# display_device_for_board.net
KiCad netlist of a schematic drawn in EAGLE
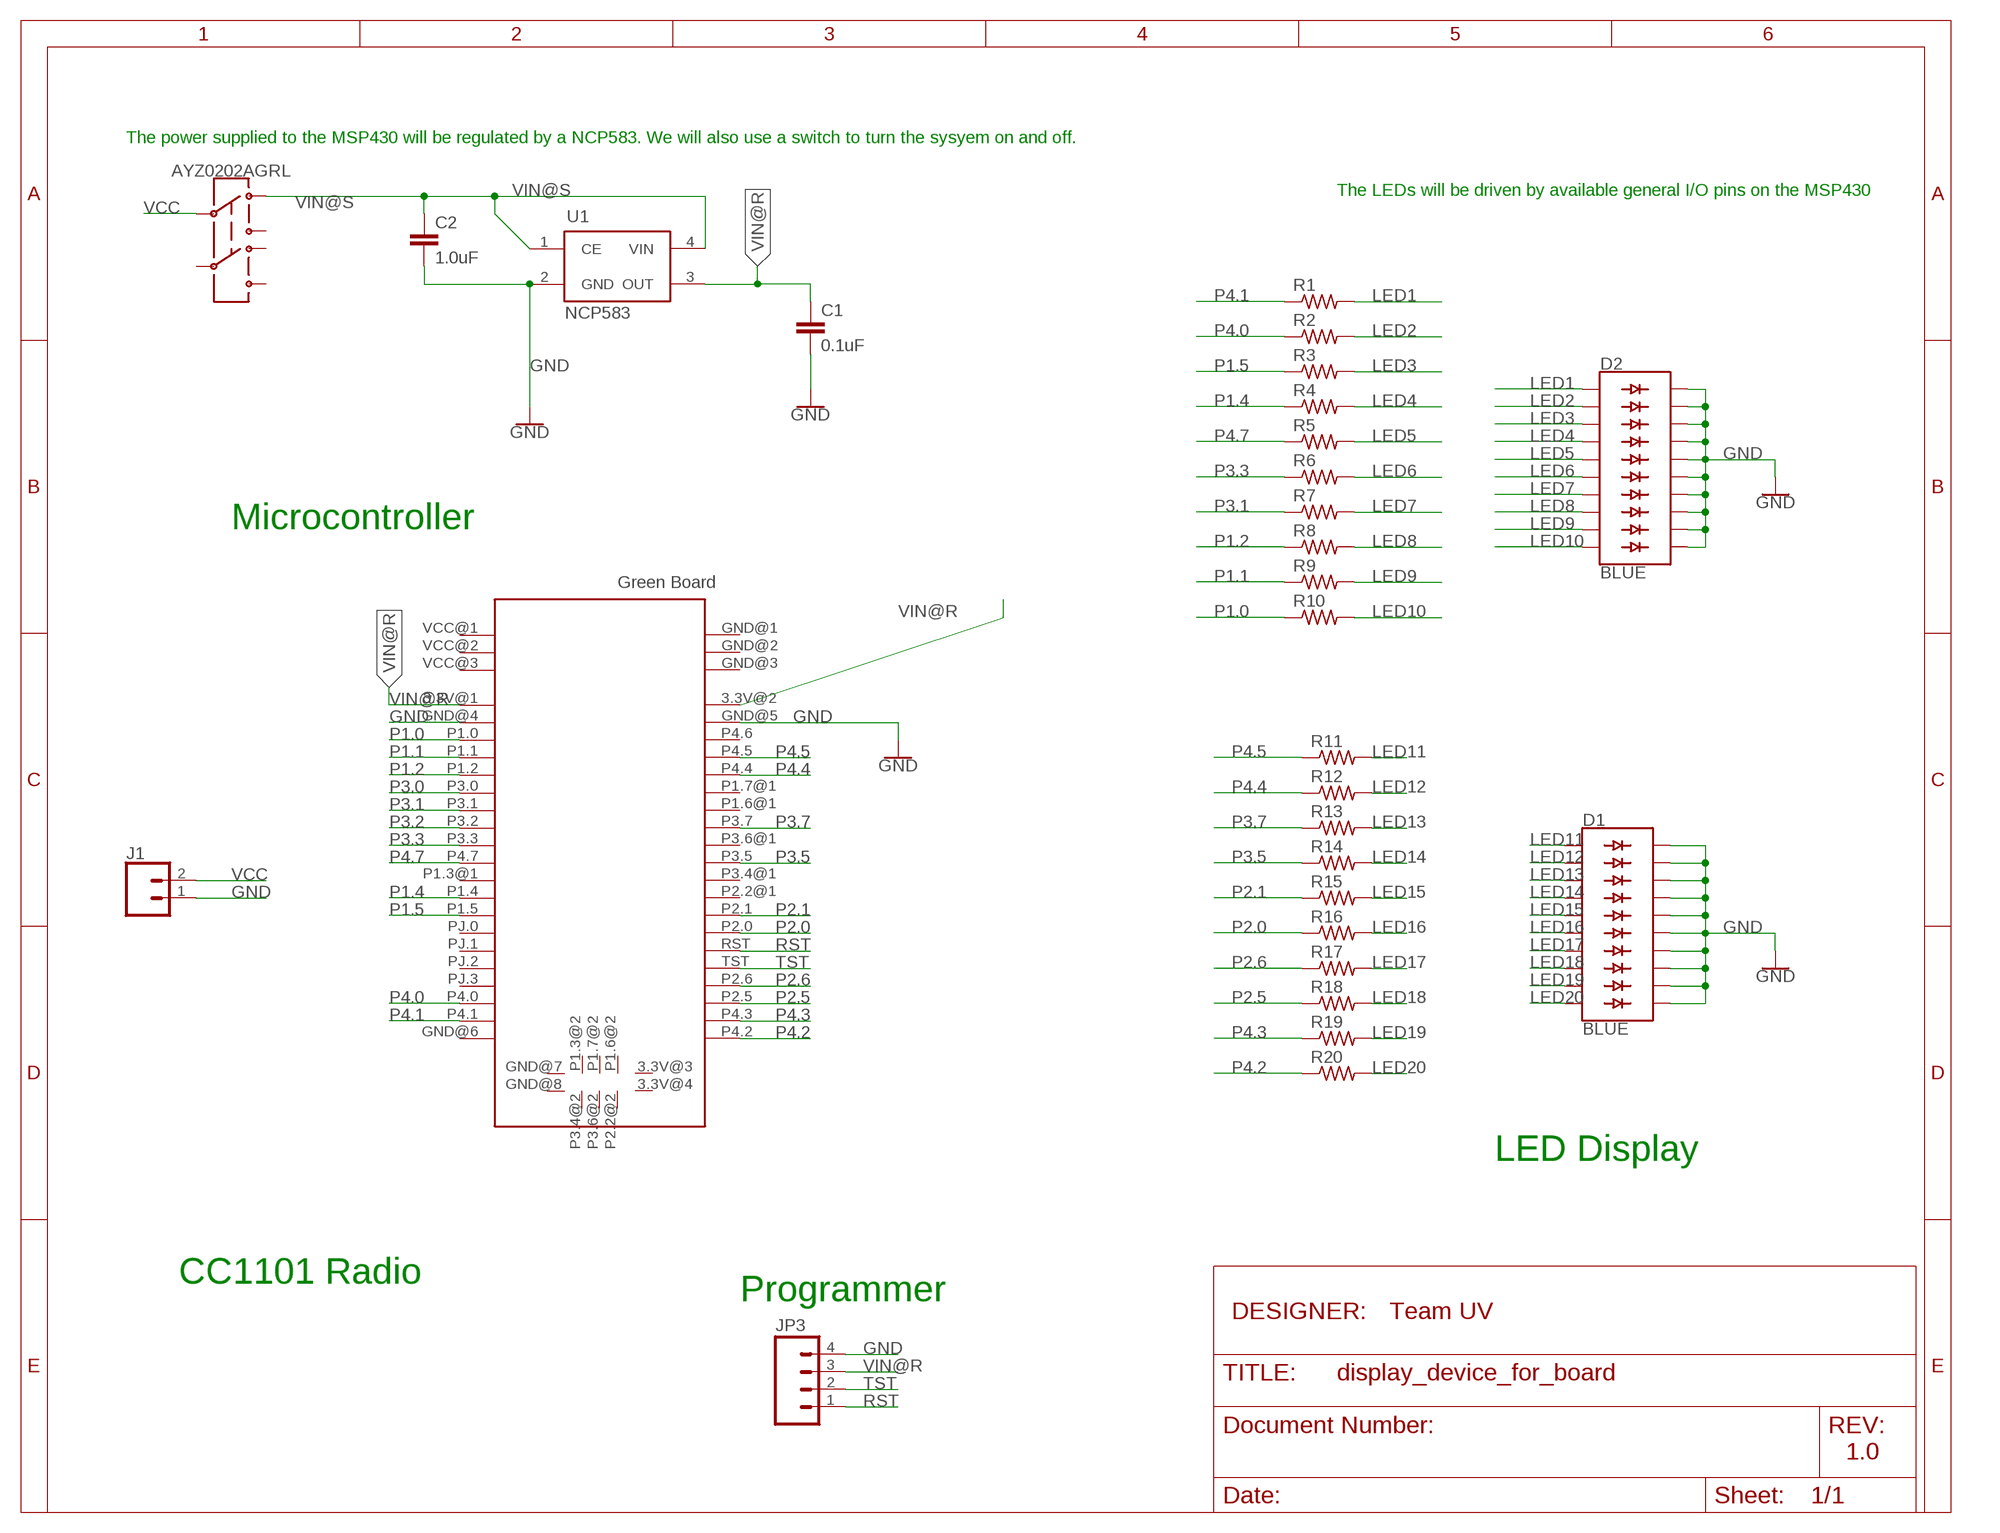
[diagram p0: schematic, sheet 1]

(export (version "E")
  (design (tool "Eeschema 10.0.6"))
  (components
    (comp (ref "AYZ0202AGRL")
      (value "SWITCH-DPDT-SMD-AYZ0202")
      (footprint "eagle-import:SWITCH_DPDT_SMD_AYZ0202")
      (libsource (lib "eagle-import") (part "SWITCH-DPDT-SMD-AYZ0202"))
    )
    (comp (ref "C1")
      (value "0.1uF")
      (footprint "eagle-import:0805")
      (libsource (lib "eagle-import") (part "1.0UF-0805-25V-(+80/-20%)"))
    )
    (comp (ref "C2")
      (value "1.0uF")
      (footprint "eagle-import:0805")
      (libsource (lib "eagle-import") (part "1.0UF-0805-25V-(+80/-20%)"))
    )
    (comp (ref "D1")
      (value "BLUE")
      (footprint "eagle-import:LED_BARGRAPH_10")
      (libsource (lib "eagle-import") (part "LED_BARGRAPH_10BLUE"))
    )
    (comp (ref "D2")
      (value "BLUE")
      (footprint "eagle-import:LED_BARGRAPH_10")
      (libsource (lib "eagle-import") (part "LED_BARGRAPH_10BLUE"))
    )
    (comp (ref "J1")
      (value "CONN_02")
      (footprint "eagle-import:1X02")
      (libsource (lib "eagle-import") (part "CONN_02"))
    )
    (comp (ref "JP3")
      (value "M04PTH")
      (footprint "eagle-import:1X04")
      (libsource (lib "eagle-import") (part "M04PTH"))
    )
    (comp (ref "R1")
      (value "R-US_R0805")
      (footprint "eagle-import:R0805")
      (libsource (lib "eagle-import") (part "R-US_R0805"))
    )
    (comp (ref "R2")
      (value "R-US_R0805")
      (footprint "eagle-import:R0805")
      (libsource (lib "eagle-import") (part "R-US_R0805"))
    )
    (comp (ref "R3")
      (value "R-US_R0805")
      (footprint "eagle-import:R0805")
      (libsource (lib "eagle-import") (part "R-US_R0805"))
    )
    (comp (ref "R4")
      (value "R-US_R0805")
      (footprint "eagle-import:R0805")
      (libsource (lib "eagle-import") (part "R-US_R0805"))
    )
    (comp (ref "R5")
      (value "R-US_R0805")
      (footprint "eagle-import:R0805")
      (libsource (lib "eagle-import") (part "R-US_R0805"))
    )
    (comp (ref "R6")
      (value "R-US_R0805")
      (footprint "eagle-import:R0805")
      (libsource (lib "eagle-import") (part "R-US_R0805"))
    )
    (comp (ref "R7")
      (value "R-US_R0805")
      (footprint "eagle-import:R0805")
      (libsource (lib "eagle-import") (part "R-US_R0805"))
    )
    (comp (ref "R8")
      (value "R-US_R0805")
      (footprint "eagle-import:R0805")
      (libsource (lib "eagle-import") (part "R-US_R0805"))
    )
    (comp (ref "R9")
      (value "R-US_R0805")
      (footprint "eagle-import:R0805")
      (libsource (lib "eagle-import") (part "R-US_R0805"))
    )
    (comp (ref "R10")
      (value "R-US_R0805")
      (footprint "eagle-import:R0805")
      (libsource (lib "eagle-import") (part "R-US_R0805"))
    )
    (comp (ref "R11")
      (value "R-US_R0805")
      (footprint "eagle-import:R0805")
      (libsource (lib "eagle-import") (part "R-US_R0805"))
    )
    (comp (ref "R12")
      (value "R-US_R0805")
      (footprint "eagle-import:R0805")
      (libsource (lib "eagle-import") (part "R-US_R0805"))
    )
    (comp (ref "R13")
      (value "R-US_R0805")
      (footprint "eagle-import:R0805")
      (libsource (lib "eagle-import") (part "R-US_R0805"))
    )
    (comp (ref "R14")
      (value "R-US_R0805")
      (footprint "eagle-import:R0805")
      (libsource (lib "eagle-import") (part "R-US_R0805"))
    )
    (comp (ref "R15")
      (value "R-US_R0805")
      (footprint "eagle-import:R0805")
      (libsource (lib "eagle-import") (part "R-US_R0805"))
    )
    (comp (ref "R16")
      (value "R-US_R0805")
      (footprint "eagle-import:R0805")
      (libsource (lib "eagle-import") (part "R-US_R0805"))
    )
    (comp (ref "R17")
      (value "R-US_R0805")
      (footprint "eagle-import:R0805")
      (libsource (lib "eagle-import") (part "R-US_R0805"))
    )
    (comp (ref "R18")
      (value "R-US_R0805")
      (footprint "eagle-import:R0805")
      (libsource (lib "eagle-import") (part "R-US_R0805"))
    )
    (comp (ref "R19")
      (value "R-US_R0805")
      (footprint "eagle-import:R0805")
      (libsource (lib "eagle-import") (part "R-US_R0805"))
    )
    (comp (ref "R20")
      (value "R-US_R0805")
      (footprint "eagle-import:R0805")
      (libsource (lib "eagle-import") (part "R-US_R0805"))
    )
    (comp (ref "U$1")
      (value "GREEDNBRD")
      (footprint "eagle-import:GREENBRD")
      (libsource (lib "eagle-import") (part "GREEDNBRD"))
    )
    (comp (ref "U1")
      (value "NCP583")
      (footprint "eagle-import:SC82-AB_1PRIMARY")
      (libsource (lib "eagle-import") (part "NCP583"))
    )
  )
  (nets
    (net (code "1") (name "/LED1") (class "Default")
      (node (ref "D2") (pin "1") (pinfunction "A_1") (pintype "passive"))
      (node (ref "R1") (pin "2") (pinfunction "2_2") (pintype "passive"))
    )
    (net (code "2") (name "/LED2") (class "Default")
      (node (ref "D2") (pin "2") (pinfunction "A1_2") (pintype "passive"))
      (node (ref "R2") (pin "2") (pinfunction "2_2") (pintype "passive"))
    )
    (net (code "3") (name "/LED3") (class "Default")
      (node (ref "D2") (pin "3") (pinfunction "A2_3") (pintype "passive"))
      (node (ref "R3") (pin "2") (pinfunction "2_2") (pintype "passive"))
    )
    (net (code "4") (name "/LED4") (class "Default")
      (node (ref "D2") (pin "4") (pinfunction "A3_4") (pintype "passive"))
      (node (ref "R4") (pin "2") (pinfunction "2_2") (pintype "passive"))
    )
    (net (code "5") (name "/LED5") (class "Default")
      (node (ref "D2") (pin "5") (pinfunction "A4_5") (pintype "passive"))
      (node (ref "R5") (pin "2") (pinfunction "2_2") (pintype "passive"))
    )
    (net (code "6") (name "/LED6") (class "Default")
      (node (ref "D2") (pin "6") (pinfunction "A5_6") (pintype "passive"))
      (node (ref "R6") (pin "2") (pinfunction "2_2") (pintype "passive"))
    )
    (net (code "7") (name "/LED7") (class "Default")
      (node (ref "D2") (pin "7") (pinfunction "A6_7") (pintype "passive"))
      (node (ref "R7") (pin "2") (pinfunction "2_2") (pintype "passive"))
    )
    (net (code "8") (name "/LED8") (class "Default")
      (node (ref "D2") (pin "8") (pinfunction "A7_8") (pintype "passive"))
      (node (ref "R8") (pin "2") (pinfunction "2_2") (pintype "passive"))
    )
    (net (code "9") (name "/LED9") (class "Default")
      (node (ref "D2") (pin "9") (pinfunction "A8_9") (pintype "passive"))
      (node (ref "R9") (pin "2") (pinfunction "2_2") (pintype "passive"))
    )
    (net (code "10") (name "/LED10") (class "Default")
      (node (ref "D2") (pin "10") (pinfunction "A9_10") (pintype "passive"))
      (node (ref "R10") (pin "2") (pinfunction "2_2") (pintype "passive"))
    )
    (net (code "11") (name "/LED11") (class "Default")
      (node (ref "D1") (pin "1") (pinfunction "A_1") (pintype "passive"))
      (node (ref "R11") (pin "2") (pinfunction "2_2") (pintype "passive"))
    )
    (net (code "12") (name "/LED12") (class "Default")
      (node (ref "D1") (pin "2") (pinfunction "A1_2") (pintype "passive"))
      (node (ref "R12") (pin "2") (pinfunction "2_2") (pintype "passive"))
    )
    (net (code "13") (name "/LED13") (class "Default")
      (node (ref "D1") (pin "3") (pinfunction "A2_3") (pintype "passive"))
      (node (ref "R13") (pin "2") (pinfunction "2_2") (pintype "passive"))
    )
    (net (code "14") (name "/LED14") (class "Default")
      (node (ref "D1") (pin "4") (pinfunction "A3_4") (pintype "passive"))
      (node (ref "R14") (pin "2") (pinfunction "2_2") (pintype "passive"))
    )
    (net (code "15") (name "/LED15") (class "Default")
      (node (ref "D1") (pin "5") (pinfunction "A4_5") (pintype "passive"))
      (node (ref "R15") (pin "2") (pinfunction "2_2") (pintype "passive"))
    )
    (net (code "16") (name "/LED16") (class "Default")
      (node (ref "D1") (pin "6") (pinfunction "A5_6") (pintype "passive"))
      (node (ref "R16") (pin "2") (pinfunction "2_2") (pintype "passive"))
    )
    (net (code "17") (name "/LED17") (class "Default")
      (node (ref "D1") (pin "7") (pinfunction "A6_7") (pintype "passive"))
      (node (ref "R17") (pin "2") (pinfunction "2_2") (pintype "passive"))
    )
    (net (code "18") (name "/LED18") (class "Default")
      (node (ref "D1") (pin "8") (pinfunction "A7_8") (pintype "passive"))
      (node (ref "R18") (pin "2") (pinfunction "2_2") (pintype "passive"))
    )
    (net (code "19") (name "/LED19") (class "Default")
      (node (ref "D1") (pin "9") (pinfunction "A8_9") (pintype "passive"))
      (node (ref "R19") (pin "2") (pinfunction "2_2") (pintype "passive"))
    )
    (net (code "20") (name "/LED20") (class "Default")
      (node (ref "D1") (pin "10") (pinfunction "A9_10") (pintype "passive"))
      (node (ref "R20") (pin "2") (pinfunction "2_2") (pintype "passive"))
    )
    (net (code "21") (name "/P1.0") (class "Default")
      (node (ref "R10") (pin "1") (pinfunction "1_1") (pintype "passive"))
      (node (ref "U$1") (pin "P1.0") (pinfunction "P1.0_P1.0") (pintype "bidirectional"))
    )
    (net (code "22") (name "/P1.1") (class "Default")
      (node (ref "R9") (pin "1") (pinfunction "1_1") (pintype "passive"))
      (node (ref "U$1") (pin "P1.1") (pinfunction "P1.1_P1.1") (pintype "bidirectional"))
    )
    (net (code "23") (name "/P1.2") (class "Default")
      (node (ref "R8") (pin "1") (pinfunction "1_1") (pintype "passive"))
      (node (ref "U$1") (pin "P1.2") (pinfunction "P1.2_P1.2") (pintype "bidirectional"))
    )
    (net (code "24") (name "/P1.4") (class "Default")
      (node (ref "R4") (pin "1") (pinfunction "1_1") (pintype "passive"))
      (node (ref "U$1") (pin "P1.4") (pinfunction "P1.4_P1.4") (pintype "bidirectional"))
    )
    (net (code "25") (name "/P1.5") (class "Default")
      (node (ref "R3") (pin "1") (pinfunction "1_1") (pintype "passive"))
      (node (ref "U$1") (pin "P1.5") (pinfunction "P1.5_P1.5") (pintype "bidirectional"))
    )
    (net (code "26") (name "/P2.0") (class "Default")
      (node (ref "R16") (pin "1") (pinfunction "1_1") (pintype "passive"))
      (node (ref "U$1") (pin "P2.0") (pinfunction "P2.0_P2.0") (pintype "bidirectional"))
    )
    (net (code "27") (name "/P2.1") (class "Default")
      (node (ref "R15") (pin "1") (pinfunction "1_1") (pintype "passive"))
      (node (ref "U$1") (pin "P2.1") (pinfunction "P2.1_P2.1") (pintype "bidirectional"))
    )
    (net (code "28") (name "/P2.5") (class "Default")
      (node (ref "R18") (pin "1") (pinfunction "1_1") (pintype "passive"))
      (node (ref "U$1") (pin "P2.5") (pinfunction "P2.5_P2.5") (pintype "bidirectional"))
    )
    (net (code "29") (name "/P2.6") (class "Default")
      (node (ref "R17") (pin "1") (pinfunction "1_1") (pintype "passive"))
      (node (ref "U$1") (pin "P2.6") (pinfunction "P2.6_P2.6") (pintype "bidirectional"))
    )
    (net (code "30") (name "/P3.0") (class "Default")
      (node (ref "U$1") (pin "P3.0") (pinfunction "P3.0_P3.0") (pintype "bidirectional"))
    )
    (net (code "31") (name "/P3.1") (class "Default")
      (node (ref "R7") (pin "1") (pinfunction "1_1") (pintype "passive"))
      (node (ref "U$1") (pin "P3.1") (pinfunction "P3.1_P3.1") (pintype "bidirectional"))
    )
    (net (code "32") (name "/P3.2") (class "Default")
      (node (ref "U$1") (pin "P3.2") (pinfunction "P3.2_P3.2") (pintype "bidirectional"))
    )
    (net (code "33") (name "/P3.3") (class "Default")
      (node (ref "R6") (pin "1") (pinfunction "1_1") (pintype "passive"))
      (node (ref "U$1") (pin "P3.3") (pinfunction "P3.3_P3.3") (pintype "bidirectional"))
    )
    (net (code "34") (name "/P3.5") (class "Default")
      (node (ref "R14") (pin "1") (pinfunction "1_1") (pintype "passive"))
      (node (ref "U$1") (pin "P3.5") (pinfunction "P3.5_P3.5") (pintype "bidirectional"))
    )
    (net (code "35") (name "/P3.7") (class "Default")
      (node (ref "R13") (pin "1") (pinfunction "1_1") (pintype "passive"))
      (node (ref "U$1") (pin "P3.7") (pinfunction "P3.7_P3.7") (pintype "bidirectional"))
    )
    (net (code "36") (name "/P4.0") (class "Default")
      (node (ref "R2") (pin "1") (pinfunction "1_1") (pintype "passive"))
      (node (ref "U$1") (pin "P4.0") (pinfunction "P4.0_P4.0") (pintype "bidirectional"))
    )
    (net (code "37") (name "/P4.1") (class "Default")
      (node (ref "R1") (pin "1") (pinfunction "1_1") (pintype "passive"))
      (node (ref "U$1") (pin "P4.1") (pinfunction "P4.1_P4.1") (pintype "bidirectional"))
    )
    (net (code "38") (name "/P4.2") (class "Default")
      (node (ref "R20") (pin "1") (pinfunction "1_1") (pintype "passive"))
      (node (ref "U$1") (pin "P4.2") (pinfunction "P4.2_P4.2") (pintype "bidirectional"))
    )
    (net (code "39") (name "/P4.3") (class "Default")
      (node (ref "R19") (pin "1") (pinfunction "1_1") (pintype "passive"))
      (node (ref "U$1") (pin "P4.3") (pinfunction "P4.3_P4.3") (pintype "bidirectional"))
    )
    (net (code "40") (name "/P4.4") (class "Default")
      (node (ref "R12") (pin "1") (pinfunction "1_1") (pintype "passive"))
      (node (ref "U$1") (pin "P4.4") (pinfunction "P4.4_P4.4") (pintype "bidirectional"))
    )
    (net (code "41") (name "/P4.5") (class "Default")
      (node (ref "R11") (pin "1") (pinfunction "1_1") (pintype "passive"))
      (node (ref "U$1") (pin "P4.5") (pinfunction "P4.5_P4.5") (pintype "bidirectional"))
    )
    (net (code "42") (name "/P4.7") (class "Default")
      (node (ref "R5") (pin "1") (pinfunction "1_1") (pintype "passive"))
      (node (ref "U$1") (pin "P4.7") (pinfunction "P4.7_P4.7") (pintype "bidirectional"))
    )
    (net (code "43") (name "/RST") (class "Default")
      (node (ref "JP3") (pin "1") (pinfunction "1_1") (pintype "passive"))
      (node (ref "U$1") (pin "RST") (pinfunction "RST_RST") (pintype "bidirectional"))
    )
    (net (code "44") (name "/TST") (class "Default")
      (node (ref "JP3") (pin "2") (pinfunction "2_2") (pintype "passive"))
      (node (ref "U$1") (pin "TST") (pinfunction "TST_TST") (pintype "bidirectional"))
    )
    (net (code "45") (name "/VCC") (class "Default")
      (node (ref "AYZ0202AGRL") (pin "2") (pinfunction "2_2") (pintype "bidirectional"))
      (node (ref "J1") (pin "2") (pinfunction "2_2") (pintype "passive"))
    )
    (net (code "46") (name "/VIN@S") (class "Default")
      (node (ref "AYZ0202AGRL") (pin "1") (pinfunction "1_1") (pintype "bidirectional"))
      (node (ref "C2") (pin "1") (pinfunction "1_1") (pintype "passive"))
      (node (ref "U1") (pin "1") (pinfunction "CE_1") (pintype "bidirectional"))
      (node (ref "U1") (pin "4") (pinfunction "VIN_4") (pintype "bidirectional"))
    )
    (net (code "47") (name "GND") (class "Default")
      (node (ref "C1") (pin "2") (pinfunction "2_2") (pintype "passive"))
      (node (ref "C2") (pin "2") (pinfunction "2_2") (pintype "passive"))
      (node (ref "D1") (pin "11") (pinfunction "C9_11") (pintype "passive"))
      (node (ref "D1") (pin "12") (pinfunction "C8_12") (pintype "passive"))
      (node (ref "D1") (pin "13") (pinfunction "C7_13") (pintype "passive"))
      (node (ref "D1") (pin "14") (pinfunction "C6_14") (pintype "passive"))
      (node (ref "D1") (pin "15") (pinfunction "C5_15") (pintype "passive"))
      (node (ref "D1") (pin "16") (pinfunction "C4_16") (pintype "passive"))
      (node (ref "D1") (pin "17") (pinfunction "C3_17") (pintype "passive"))
      (node (ref "D1") (pin "18") (pinfunction "C2_18") (pintype "passive"))
      (node (ref "D1") (pin "19") (pinfunction "C1_19") (pintype "passive"))
      (node (ref "D1") (pin "20") (pinfunction "C_20") (pintype "passive"))
      (node (ref "D2") (pin "11") (pinfunction "C9_11") (pintype "passive"))
      (node (ref "D2") (pin "12") (pinfunction "C8_12") (pintype "passive"))
      (node (ref "D2") (pin "13") (pinfunction "C7_13") (pintype "passive"))
      (node (ref "D2") (pin "14") (pinfunction "C6_14") (pintype "passive"))
      (node (ref "D2") (pin "15") (pinfunction "C5_15") (pintype "passive"))
      (node (ref "D2") (pin "16") (pinfunction "C4_16") (pintype "passive"))
      (node (ref "D2") (pin "17") (pinfunction "C3_17") (pintype "passive"))
      (node (ref "D2") (pin "18") (pinfunction "C2_18") (pintype "passive"))
      (node (ref "D2") (pin "19") (pinfunction "C1_19") (pintype "passive"))
      (node (ref "D2") (pin "20") (pinfunction "C_20") (pintype "passive"))
      (node (ref "J1") (pin "1") (pinfunction "1_1") (pintype "passive"))
      (node (ref "JP3") (pin "4") (pinfunction "4_4") (pintype "passive"))
      (node (ref "U$1") (pin "GND@4") (pinfunction "GND_GND@4") (pintype "bidirectional"))
      (node (ref "U$1") (pin "GND@5") (pinfunction "GND_GND@5") (pintype "bidirectional"))
      (node (ref "U1") (pin "2") (pinfunction "GND_2") (pintype "bidirectional"))
    )
    (net (code "48") (name "VIN@R") (class "Default")
      (node (ref "C1") (pin "1") (pinfunction "1_1") (pintype "passive"))
      (node (ref "JP3") (pin "3") (pinfunction "3_3") (pintype "passive"))
      (node (ref "U$1") (pin "3.3V@1") (pinfunction "3.3V_3.3V@1") (pintype "bidirectional"))
      (node (ref "U$1") (pin "3.3V@2") (pinfunction "3.3V_3.3V@2") (pintype "bidirectional"))
      (node (ref "U1") (pin "3") (pinfunction "OUT_3") (pintype "bidirectional"))
    )
    (net (code "49") (name "unconnected-(AYZ0202AGRL-Pad3)") (class "Default")
      (node (ref "AYZ0202AGRL") (pin "3") (pinfunction "3_3") (pintype "bidirectional"))
    )
    (net (code "50") (name "unconnected-(AYZ0202AGRL-Pad4)") (class "Default")
      (node (ref "AYZ0202AGRL") (pin "4") (pinfunction "4_4") (pintype "bidirectional"))
    )
    (net (code "51") (name "unconnected-(AYZ0202AGRL-Pad5)") (class "Default")
      (node (ref "AYZ0202AGRL") (pin "5") (pinfunction "5_5") (pintype "bidirectional"))
    )
    (net (code "52") (name "unconnected-(AYZ0202AGRL-Pad6)") (class "Default")
      (node (ref "AYZ0202AGRL") (pin "6") (pinfunction "6_6") (pintype "bidirectional"))
    )
    (net (code "53") (name "unconnected-(U$1-3.3V-Pad3.3V@3)") (class "Default")
      (node (ref "U$1") (pin "3.3V@3") (pinfunction "3.3V_3.3V@3") (pintype "bidirectional"))
    )
    (net (code "54") (name "unconnected-(U$1-3.3V-Pad3.3V@4)") (class "Default")
      (node (ref "U$1") (pin "3.3V@4") (pinfunction "3.3V_3.3V@4") (pintype "bidirectional"))
    )
    (net (code "55") (name "unconnected-(U$1-GND-PadGND@1)") (class "Default")
      (node (ref "U$1") (pin "GND@1") (pinfunction "GND_GND@1") (pintype "bidirectional"))
    )
    (net (code "56") (name "unconnected-(U$1-GND-PadGND@2)") (class "Default")
      (node (ref "U$1") (pin "GND@2") (pinfunction "GND_GND@2") (pintype "bidirectional"))
    )
    (net (code "57") (name "unconnected-(U$1-GND-PadGND@3)") (class "Default")
      (node (ref "U$1") (pin "GND@3") (pinfunction "GND_GND@3") (pintype "bidirectional"))
    )
    (net (code "58") (name "unconnected-(U$1-GND-PadGND@6)") (class "Default")
      (node (ref "U$1") (pin "GND@6") (pinfunction "GND_GND@6") (pintype "bidirectional"))
    )
    (net (code "59") (name "unconnected-(U$1-GND-PadGND@7)") (class "Default")
      (node (ref "U$1") (pin "GND@7") (pinfunction "GND_GND@7") (pintype "bidirectional"))
    )
    (net (code "60") (name "unconnected-(U$1-GND-PadGND@8)") (class "Default")
      (node (ref "U$1") (pin "GND@8") (pinfunction "GND_GND@8") (pintype "bidirectional"))
    )
    (net (code "61") (name "unconnected-(U$1-P1.3-PadP1.3@1)") (class "Default")
      (node (ref "U$1") (pin "P1.3@1") (pinfunction "P1.3_P1.3@1") (pintype "bidirectional"))
    )
    (net (code "62") (name "unconnected-(U$1-P1.3-PadP1.3@2)") (class "Default")
      (node (ref "U$1") (pin "P1.3@2") (pinfunction "P1.3_P1.3@2") (pintype "bidirectional"))
    )
    (net (code "63") (name "unconnected-(U$1-P1.6-PadP1.6@1)") (class "Default")
      (node (ref "U$1") (pin "P1.6@1") (pinfunction "P1.6_P1.6@1") (pintype "bidirectional"))
    )
    (net (code "64") (name "unconnected-(U$1-P1.6-PadP1.6@2)") (class "Default")
      (node (ref "U$1") (pin "P1.6@2") (pinfunction "P1.6_P1.6@2") (pintype "bidirectional"))
    )
    (net (code "65") (name "unconnected-(U$1-P1.7-PadP1.7@1)") (class "Default")
      (node (ref "U$1") (pin "P1.7@1") (pinfunction "P1.7_P1.7@1") (pintype "bidirectional"))
    )
    (net (code "66") (name "unconnected-(U$1-P1.7-PadP1.7@2)") (class "Default")
      (node (ref "U$1") (pin "P1.7@2") (pinfunction "P1.7_P1.7@2") (pintype "bidirectional"))
    )
    (net (code "67") (name "unconnected-(U$1-P2.2-PadP2.2@1)") (class "Default")
      (node (ref "U$1") (pin "P2.2@1") (pinfunction "P2.2_P2.2@1") (pintype "bidirectional"))
    )
    (net (code "68") (name "unconnected-(U$1-P2.2-PadP2.2@2)") (class "Default")
      (node (ref "U$1") (pin "P2.2@2") (pinfunction "P2.2_P2.2@2") (pintype "bidirectional"))
    )
    (net (code "69") (name "unconnected-(U$1-P3.4-PadP3.4@1)") (class "Default")
      (node (ref "U$1") (pin "P3.4@1") (pinfunction "P3.4_P3.4@1") (pintype "bidirectional"))
    )
    (net (code "70") (name "unconnected-(U$1-P3.4-PadP3.4@2)") (class "Default")
      (node (ref "U$1") (pin "P3.4@2") (pinfunction "P3.4_P3.4@2") (pintype "bidirectional"))
    )
    (net (code "71") (name "unconnected-(U$1-P3.6-PadP3.6@1)") (class "Default")
      (node (ref "U$1") (pin "P3.6@1") (pinfunction "P3.6_P3.6@1") (pintype "bidirectional"))
    )
    (net (code "72") (name "unconnected-(U$1-P3.6-PadP3.6@2)") (class "Default")
      (node (ref "U$1") (pin "P3.6@2") (pinfunction "P3.6_P3.6@2") (pintype "bidirectional"))
    )
    (net (code "73") (name "unconnected-(U$1-PadP4.6)") (class "Default")
      (node (ref "U$1") (pin "P4.6") (pinfunction "P4.6_P4.6") (pintype "bidirectional"))
    )
    (net (code "74") (name "unconnected-(U$1-PadPJ.0)") (class "Default")
      (node (ref "U$1") (pin "PJ.0") (pinfunction "PJ.0_PJ.0") (pintype "bidirectional"))
    )
    (net (code "75") (name "unconnected-(U$1-PadPJ.1)") (class "Default")
      (node (ref "U$1") (pin "PJ.1") (pinfunction "PJ.1_PJ.1") (pintype "bidirectional"))
    )
    (net (code "76") (name "unconnected-(U$1-PadPJ.2)") (class "Default")
      (node (ref "U$1") (pin "PJ.2") (pinfunction "PJ.2_PJ.2") (pintype "bidirectional"))
    )
    (net (code "77") (name "unconnected-(U$1-PadPJ.3)") (class "Default")
      (node (ref "U$1") (pin "PJ.3") (pinfunction "PJ.3_PJ.3") (pintype "bidirectional"))
    )
    (net (code "78") (name "unconnected-(U$1-VCC-PadVCC@1)") (class "Default")
      (node (ref "U$1") (pin "VCC@1") (pinfunction "VCC_VCC@1") (pintype "bidirectional"))
    )
    (net (code "79") (name "unconnected-(U$1-VCC-PadVCC@2)") (class "Default")
      (node (ref "U$1") (pin "VCC@2") (pinfunction "VCC_VCC@2") (pintype "bidirectional"))
    )
    (net (code "80") (name "unconnected-(U$1-VCC-PadVCC@3)") (class "Default")
      (node (ref "U$1") (pin "VCC@3") (pinfunction "VCC_VCC@3") (pintype "bidirectional"))
    )
  )
)
